# Sheet1.net
KiCad netlist of a schematic drawn in Altium Designer
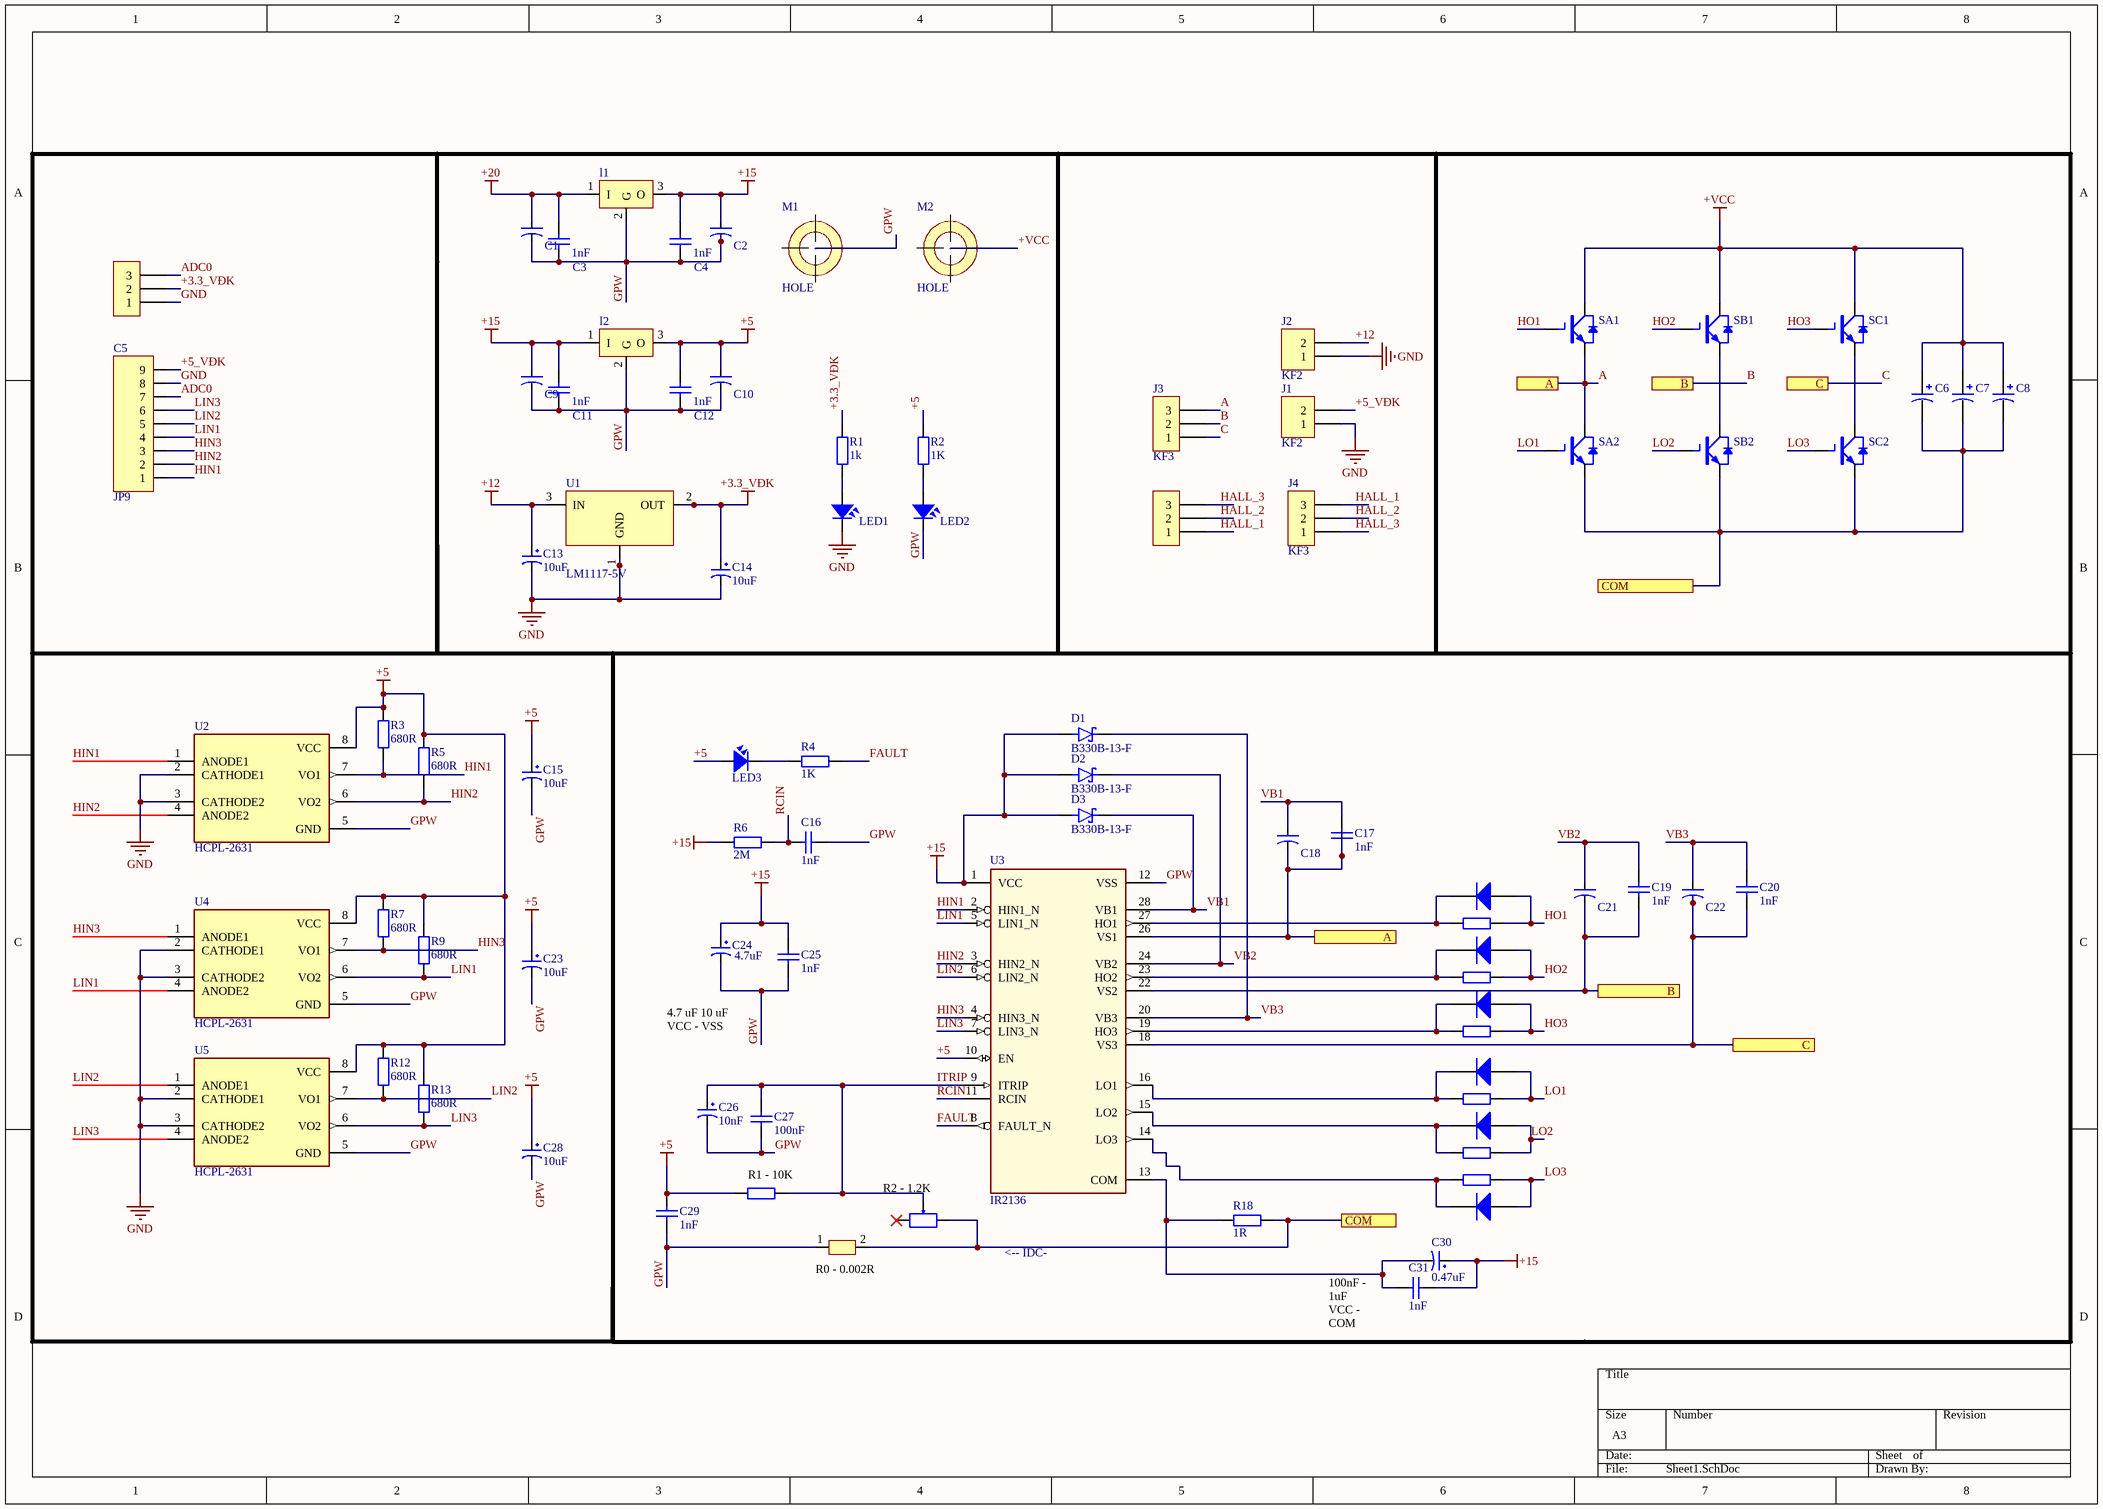
[diagram p0: Sheet1.SchDoc]

(export (version "E")
  (design (tool "Eeschema 10.0.6"))
  (components
    (comp (ref "*1")
      (value "Component_1")
      (footprint "PCBComponent_1")
      (libsource (lib "Shunt") (part "Component_1"))
    )
    (comp (ref "C1")
      (value "CN-ALU-DIP")
      (footprint "CA-ALU-5")
      (description "Capacitor (Semiconductor SIM Model)")
      (fields (field (name "PUBLISHER") "Altium Limited"))
      (libsource (lib "TechMT.VN_Lib_Project v2") (part "CN-ALU-DIP"))
    )
    (comp (ref "C2")
      (value "CN-ALU-DIP")
      (footprint "CA-ALU-5")
      (description "Capacitor (Semiconductor SIM Model)")
      (fields (field (name "PUBLISHER") "Altium Limited"))
      (libsource (lib "TechMT.VN_Lib_Project v2") (part "CN-ALU-DIP"))
    )
    (comp (ref "C3")
      (value "1nF")
      (footprint "tu 1206")
      (description "Dán")
      (libsource (lib "Altium_Lib_by_KhueNguyenCreator") (part "Tu 1206 470pF 50V 10%"))
    )
    (comp (ref "C4")
      (value "1nF")
      (footprint "tu 1206")
      (description "Dán")
      (libsource (lib "Altium_Lib_by_KhueNguyenCreator") (part "Tu 1206 470pF 50V 10%"))
    )
    (comp (ref "C5")
      (value "JP9")
      (footprint "JP9-C1T")
      (description "WR-PHD 2.54 mm Angled Socket Header")
      (fields
        (field (name "MANUFACTURER") "Würth Elektronik eiSos GmbH")
        (field (name "PARTNO") "613009143121")
        (field (name "CREATED BY") "Karrer Zheng")
      )
      (libsource (lib "TechMT.VN_Lib_Project v2") (part "JP9"))
    )
    (comp (ref "C6")
      (value "150uF - 450V")
      (footprint "CAP_ALUM_D160_S75_H250")
      (description "CAP ALUM 1000uF 20% 63V RADIAL")
      (fields (field (name "MPN") "CLA4514"))
      (libsource (lib "BYTECH_HW_LIB_2019 (1)") (part "CLA4514"))
    )
    (comp (ref "C7")
      (value "150uF - 450V")
      (footprint "CAP_ALUM_D160_S75_H250")
      (description "CAP ALUM 1000uF 20% 63V RADIAL")
      (fields (field (name "MPN") "CLA4514"))
      (libsource (lib "BYTECH_HW_LIB_2019 (1)") (part "CLA4514"))
    )
    (comp (ref "C8")
      (value "150uF - 450V")
      (footprint "CAP_ALUM_D160_S75_H250")
      (description "CAP ALUM 1000uF 20% 63V RADIAL")
      (fields (field (name "MPN") "CLA4514"))
      (libsource (lib "BYTECH_HW_LIB_2019 (1)") (part "CLA4514"))
    )
    (comp (ref "C9")
      (value "CN-ALU-DIP")
      (footprint "CA-ALU-5")
      (description "Capacitor (Semiconductor SIM Model)")
      (fields (field (name "PUBLISHER") "Altium Limited"))
      (libsource (lib "TechMT.VN_Lib_Project v2") (part "CN-ALU-DIP"))
    )
    (comp (ref "C10")
      (value "CN-ALU-DIP")
      (footprint "CA-ALU-5")
      (description "Capacitor (Semiconductor SIM Model)")
      (fields (field (name "PUBLISHER") "Altium Limited"))
      (libsource (lib "TechMT.VN_Lib_Project v2") (part "CN-ALU-DIP"))
    )
    (comp (ref "C11")
      (value "1nF")
      (footprint "tu 1206")
      (description "Dán")
      (libsource (lib "Altium_Lib_by_KhueNguyenCreator") (part "Tu 1206 470pF 50V 10%"))
    )
    (comp (ref "C12")
      (value "1nF")
      (footprint "tu 1206")
      (description "Dán")
      (libsource (lib "Altium_Lib_by_KhueNguyenCreator") (part "Tu 1206 470pF 50V 10%"))
    )
    (comp (ref "C13")
      (value "10uF")
      (footprint "tu tantalum smd3216")
      (description "Dán")
      (libsource (lib "Altium_Lib_by_KhueNguyenCreator") (part "Tu tantalum 10uF 16V SMD3216"))
    )
    (comp (ref "C14")
      (value "10uF")
      (footprint "tu tantalum smd3216")
      (description "Dán")
      (libsource (lib "Altium_Lib_by_KhueNguyenCreator") (part "Tu tantalum 10uF 16V SMD3216"))
    )
    (comp (ref "C15")
      (value "10uF")
      (footprint "tu tantalum smd3216")
      (description "Dán")
      (libsource (lib "Altium_Lib_by_KhueNguyenCreator") (part "Tu tantalum 10uF 16V SMD3216"))
    )
    (comp (ref "C16")
      (value "1nF")
      (footprint "tu 1206")
      (description "Dán")
      (libsource (lib "Altium_Lib_by_KhueNguyenCreator") (part "Tu 1206 470pF 50V 10%"))
    )
    (comp (ref "C17")
      (value "1nF")
      (footprint "tu 1206")
      (description "Dán")
      (libsource (lib "Altium_Lib_by_KhueNguyenCreator") (part "Tu 1206 470pF 50V 10%"))
    )
    (comp (ref "C18")
      (value "CN-ALU-DIP")
      (footprint "CA-ALU-5")
      (description "Capacitor (Semiconductor SIM Model)")
      (fields (field (name "PUBLISHER") "Altium Limited"))
      (libsource (lib "TechMT.VN_Lib_Project v2") (part "CN-ALU-DIP"))
    )
    (comp (ref "C19")
      (value "1nF")
      (footprint "tu 1206")
      (description "Dán")
      (libsource (lib "Altium_Lib_by_KhueNguyenCreator") (part "Tu 1206 470pF 50V 10%"))
    )
    (comp (ref "C20")
      (value "1nF")
      (footprint "tu 1206")
      (description "Dán")
      (libsource (lib "Altium_Lib_by_KhueNguyenCreator") (part "Tu 1206 470pF 50V 10%"))
    )
    (comp (ref "C21")
      (value "CN-ALU-DIP")
      (footprint "CA-ALU-5")
      (description "Capacitor (Semiconductor SIM Model)")
      (fields (field (name "PUBLISHER") "Altium Limited"))
      (libsource (lib "TechMT.VN_Lib_Project v2") (part "CN-ALU-DIP"))
    )
    (comp (ref "C22")
      (value "CN-ALU-DIP")
      (footprint "CA-ALU-5")
      (description "Capacitor (Semiconductor SIM Model)")
      (fields (field (name "PUBLISHER") "Altium Limited"))
      (libsource (lib "TechMT.VN_Lib_Project v2") (part "CN-ALU-DIP"))
    )
    (comp (ref "C23")
      (value "10uF")
      (footprint "tu tantalum smd3216")
      (description "Dán")
      (libsource (lib "Altium_Lib_by_KhueNguyenCreator") (part "Tu tantalum 10uF 16V SMD3216"))
    )
    (comp (ref "C24")
      (value "4.7uF")
      (footprint "tu tantalum smd3216")
      (description "Dán")
      (libsource (lib "Altium_Lib_by_KhueNguyenCreator") (part "Tu tantalum 10uF 16V SMD3216"))
    )
    (comp (ref "C25")
      (value "1nF")
      (footprint "tu 1206")
      (description "Dán")
      (libsource (lib "Altium_Lib_by_KhueNguyenCreator") (part "Tu 1206 470pF 50V 10%"))
    )
    (comp (ref "C26")
      (value "10nF")
      (footprint "tu tantalum smd3216")
      (description "Dán")
      (libsource (lib "Altium_Lib_by_KhueNguyenCreator") (part "Tu tantalum 10uF 16V SMD3216"))
    )
    (comp (ref "C27")
      (value "100nF")
      (footprint "tu 1206")
      (description "Dán")
      (libsource (lib "Altium_Lib_by_KhueNguyenCreator") (part "Tu 1206 470pF 50V 10%"))
    )
    (comp (ref "C28")
      (value "10uF")
      (footprint "tu tantalum smd3216")
      (description "Dán")
      (libsource (lib "Altium_Lib_by_KhueNguyenCreator") (part "Tu tantalum 10uF 16V SMD3216"))
    )
    (comp (ref "C29")
      (value "1nF")
      (footprint "tu 1206")
      (description "Dán")
      (libsource (lib "Altium_Lib_by_KhueNguyenCreator") (part "Tu 1206 470pF 50V 10%"))
    )
    (comp (ref "C30")
      (value "0.47uF")
      (footprint "tu tantalum smd3216")
      (description "Dán")
      (libsource (lib "") (part "Tu tantalum 10uF 16V SMD3216_1"))
    )
    (comp (ref "C31")
      (value "1nF")
      (footprint "tu 1206")
      (description "Dán")
      (libsource (lib "Altium_Lib_by_KhueNguyenCreator") (part "Tu 1206 470pF 50V 10%"))
    )
    (comp (ref "D1")
      (value "B330B-13-F")
      (footprint "DIOM5336X240N")
      (description "Diode Schottky 30 V 3A Surface Mount SMB")
      (fields (field (name "MF") "Diodes Inc."))
      (libsource (lib "Do214AA_SMB_Diode") (part "B330B-13-F"))
    )
    (comp (ref "D2")
      (value "B330B-13-F")
      (footprint "DIOM5336X240N")
      (description "Diode Schottky 30 V 3A Surface Mount SMB")
      (fields (field (name "MF") "Diodes Inc."))
      (libsource (lib "Do214AA_SMB_Diode") (part "B330B-13-F"))
    )
    (comp (ref "D3")
      (value "B330B-13-F")
      (footprint "DIOM5336X240N")
      (description "Diode Schottky 30 V 3A Surface Mount SMB")
      (fields (field (name "MF") "Diodes Inc."))
      (libsource (lib "Do214AA_SMB_Diode") (part "B330B-13-F"))
    )
    (comp (ref "D4")
      (value "SS14")
      (footprint "DIODE SMA")
      (description "Dán")
      (libsource (lib "Altium_Lib_by_KhueNguyenCreator") (part "Diode SS14 ( 1N5819)"))
    )
    (comp (ref "D5")
      (value "SS14")
      (footprint "DIODE SMA")
      (description "Dán")
      (libsource (lib "Altium_Lib_by_KhueNguyenCreator") (part "Diode SS14 ( 1N5819)"))
    )
    (comp (ref "D6")
      (value "SS14")
      (footprint "DIODE SMA")
      (description "Dán")
      (libsource (lib "Altium_Lib_by_KhueNguyenCreator") (part "Diode SS14 ( 1N5819)"))
    )
    (comp (ref "D7")
      (value "SS14")
      (footprint "DIODE SMA")
      (description "Dán")
      (libsource (lib "Altium_Lib_by_KhueNguyenCreator") (part "Diode SS14 ( 1N5819)"))
    )
    (comp (ref "D8")
      (value "SS14")
      (footprint "DIODE SMA")
      (description "Dán")
      (libsource (lib "Altium_Lib_by_KhueNguyenCreator") (part "Diode SS14 ( 1N5819)"))
    )
    (comp (ref "D9")
      (value "SS14")
      (footprint "DIODE SMA")
      (description "Dán")
      (libsource (lib "Altium_Lib_by_KhueNguyenCreator") (part "Diode SS14 ( 1N5819)"))
    )
    (comp (ref "H1")
      (value "Header 3P 2.54 Duc Thang")
      (footprint "XH2.54M-3")
      (description "Cắm")
      (libsource (lib "Altium_Lib_by_KhueNguyenCreator") (part "Header 3P 2.54 Duc Thang"))
    )
    (comp (ref "H2")
      (value "Header 3P 2.54 Duc Thang")
      (footprint "XH2.54M-3")
      (description "Cắm")
      (libsource (lib "Altium_Lib_by_KhueNguyenCreator") (part "Header 3P 2.54 Duc Thang"))
    )
    (comp (ref "J1")
      (value "KF2")
      (footprint "KF2-3.5")
      (fields
        (field (name "MANUFACTURER") "Würth Elektronik eiSos GmbH")
        (field (name "PARTNO") "691103110002")
        (field (name "CREATED BY") "Karrer Zheng")
      )
      (libsource (lib "TechMT.VN_Lib_Project v2") (part "KF2"))
    )
    (comp (ref "J2")
      (value "KF2")
      (footprint "KF2-3.5")
      (fields
        (field (name "MANUFACTURER") "Würth Elektronik eiSos GmbH")
        (field (name "PARTNO") "691103110002")
        (field (name "CREATED BY") "Karrer Zheng")
      )
      (libsource (lib "TechMT.VN_Lib_Project v2") (part "KF2"))
    )
    (comp (ref "J3")
      (value "KF3")
      (footprint "KF3-8.5")
      (fields
        (field (name "MANUFACTURER") "Würth Elektronik eiSos GmbH")
        (field (name "PARTNO") "691103110003")
        (field (name "CREATED BY") "Karrer Zheng")
      )
      (libsource (lib "TechMT.VN_Lib_Project v2") (part "KF3"))
    )
    (comp (ref "J4")
      (value "KF3")
      (footprint "KF3-3.5")
      (fields
        (field (name "MANUFACTURER") "Würth Elektronik eiSos GmbH")
        (field (name "PARTNO") "691103110003")
        (field (name "CREATED BY") "Karrer Zheng")
      )
      (libsource (lib "TechMT.VN_Lib_Project v2") (part "KF3"))
    )
    (comp (ref "l1")
      (value "LM78xx")
      (footprint "TO220-123")
      (description "Positive Voltage Regulator")
      (fields (field (name "PUBLISHER") "Altium Limited"))
      (libsource (lib "TechMT.VN_Lib_Project v2") (part "LM78xx"))
    )
    (comp (ref "l2")
      (value "LM78xx")
      (footprint "TO220-123")
      (description "Positive Voltage Regulator")
      (fields (field (name "PUBLISHER") "Altium Limited"))
      (libsource (lib "TechMT.VN_Lib_Project v2") (part "LM78xx"))
    )
    (comp (ref "LED1")
      (value "LED")
      (footprint "LED-1206-Blue")
      (libsource (lib "TechMT.VN_Lib_Project v2") (part "LED SMD"))
    )
    (comp (ref "LED2")
      (value "LED")
      (footprint "LED-1206-Blue")
      (libsource (lib "TechMT.VN_Lib_Project v2") (part "LED SMD"))
    )
    (comp (ref "LED3")
      (value "LED")
      (footprint "LED-1206-Blue")
      (libsource (lib "TechMT.VN_Lib_Project v2") (part "LED SMD"))
    )
    (comp (ref "M1")
      (value "HOLE")
      (footprint "HOLE_3MM_5MM")
      (description "HOLE 2_4/2_5/3_5/3_6")
      (fields (field (name "MPN") "None"))
      (libsource (lib "BYTECH_HW_LIB_2019 (1)") (part "HOLE_2_4/2_5/3_5/3_6"))
    )
    (comp (ref "M2")
      (value "HOLE")
      (footprint "HOLE_3MM_5MM")
      (description "HOLE 2_4/2_5/3_5/3_6")
      (fields (field (name "MPN") "None"))
      (libsource (lib "BYTECH_HW_LIB_2019 (1)") (part "HOLE_2_4/2_5/3_5/3_6"))
    )
    (comp (ref "R1")
      (value "1k")
      (footprint "tro smd 1206")
      (description "Dán")
      (libsource (lib "Altium_Lib_by_KhueNguyenCreator") (part "Tro 1206 5% 680R"))
    )
    (comp (ref "R2")
      (value "1K")
      (footprint "tro smd 1206")
      (description "Dán")
      (libsource (lib "Altium_Lib_by_KhueNguyenCreator") (part "Tro 1206 5% 680R"))
    )
    (comp (ref "R3")
      (value "680R")
      (footprint "tro smd 1206")
      (description "Dán")
      (libsource (lib "Altium_Lib_by_KhueNguyenCreator") (part "Tro 1206 5% 680R"))
    )
    (comp (ref "R4")
      (value "1K")
      (footprint "tro smd 1206")
      (description "Dán")
      (libsource (lib "Altium_Lib_by_KhueNguyenCreator") (part "Tro 1206 5% 680R"))
    )
    (comp (ref "R5")
      (value "680R")
      (footprint "tro smd 1206")
      (description "Dán")
      (libsource (lib "Altium_Lib_by_KhueNguyenCreator") (part "Tro 1206 5% 680R"))
    )
    (comp (ref "R6")
      (value "2M")
      (footprint "tro smd 1206")
      (description "Dán")
      (libsource (lib "Altium_Lib_by_KhueNguyenCreator") (part "Tro 1206 5% 680R"))
    )
    (comp (ref "R7")
      (value "680R")
      (footprint "tro smd 1206")
      (description "Dán")
      (libsource (lib "Altium_Lib_by_KhueNguyenCreator") (part "Tro 1206 5% 680R"))
    )
    (comp (ref "R8")
      (value "680R")
      (footprint "tro smd 1206")
      (description "Dán")
      (libsource (lib "Altium_Lib_by_KhueNguyenCreator") (part "Tro 1206 5% 680R"))
    )
    (comp (ref "R9")
      (value "680R")
      (footprint "tro smd 1206")
      (description "Dán")
      (libsource (lib "Altium_Lib_by_KhueNguyenCreator") (part "Tro 1206 5% 680R"))
    )
    (comp (ref "R10")
      (value "680R")
      (footprint "tro smd 1206")
      (description "Dán")
      (libsource (lib "Altium_Lib_by_KhueNguyenCreator") (part "Tro 1206 5% 680R"))
    )
    (comp (ref "R11")
      (value "680R")
      (footprint "tro smd 1206")
      (description "Dán")
      (libsource (lib "Altium_Lib_by_KhueNguyenCreator") (part "Tro 1206 5% 680R"))
    )
    (comp (ref "R12")
      (value "680R")
      (footprint "tro smd 1206")
      (description "Dán")
      (libsource (lib "Altium_Lib_by_KhueNguyenCreator") (part "Tro 1206 5% 680R"))
    )
    (comp (ref "R13")
      (value "680R")
      (footprint "tro smd 1206")
      (description "Dán")
      (libsource (lib "Altium_Lib_by_KhueNguyenCreator") (part "Tro 1206 5% 680R"))
    )
    (comp (ref "R14")
      (value "680R")
      (footprint "tro smd 1206")
      (description "Dán")
      (libsource (lib "Altium_Lib_by_KhueNguyenCreator") (part "Tro 1206 5% 680R"))
    )
    (comp (ref "R15")
      (value "680R")
      (footprint "tro smd 1206")
      (description "Dán")
      (libsource (lib "Altium_Lib_by_KhueNguyenCreator") (part "Tro 1206 5% 680R"))
    )
    (comp (ref "R16")
      (value "680R")
      (footprint "tro smd 1206")
      (description "Dán")
      (libsource (lib "Altium_Lib_by_KhueNguyenCreator") (part "Tro 1206 5% 680R"))
    )
    (comp (ref "R17")
      (value "5.1K")
      (footprint "tro smd 1206")
      (description "Dán")
      (libsource (lib "Altium_Lib_by_KhueNguyenCreator") (part "Tro 1206 5% 680R"))
    )
    (comp (ref "R18")
      (value "1R")
      (footprint "tro smd 1206")
      (description "Dán")
      (libsource (lib "Altium_Lib_by_KhueNguyenCreator") (part "Tro 1206 5% 680R"))
    )
    (comp (ref "R19")
      (value "6K")
      (footprint "Bien Tro Vi Chinh Dung")
      (description "Cắm")
      (libsource (lib "Altium_Lib_by_KhueNguyenCreator") (part "Bien Tro Tinh Chinh 100R Dung"))
    )
    (comp (ref "SA1")
      (value "FGA25N120ANTD")
      (footprint "TO545P500X1560X1990-3P")
      (description "IGBT NPT and Trench 1200V 50A 312W Through Hole TO-3P")
      (fields
        (field (name "DIGI-KEY_PART_NUMBER") "FGA25N120ANTDTU-ND")
        (field (name "MF") "ON Semiconductor")
      )
      (libsource (lib "IGBT 5.45") (part "FGA25N120ANTD"))
    )
    (comp (ref "SA2")
      (value "FGA25N120ANTD")
      (footprint "TO545P500X1560X1990-3P")
      (description "IGBT NPT and Trench 1200V 50A 312W Through Hole TO-3P")
      (fields
        (field (name "DIGI-KEY_PART_NUMBER") "FGA25N120ANTDTU-ND")
        (field (name "MF") "ON Semiconductor")
      )
      (libsource (lib "IGBT 5.45") (part "FGA25N120ANTD"))
    )
    (comp (ref "SB1")
      (value "FGA25N120ANTD")
      (footprint "TO545P500X1560X1990-3P")
      (description "IGBT NPT and Trench 1200V 50A 312W Through Hole TO-3P")
      (fields
        (field (name "DIGI-KEY_PART_NUMBER") "FGA25N120ANTDTU-ND")
        (field (name "MF") "ON Semiconductor")
      )
      (libsource (lib "IGBT 5.45") (part "FGA25N120ANTD"))
    )
    (comp (ref "SB2")
      (value "FGA25N120ANTD")
      (footprint "TO545P500X1560X1990-3P")
      (description "IGBT NPT and Trench 1200V 50A 312W Through Hole TO-3P")
      (fields
        (field (name "DIGI-KEY_PART_NUMBER") "FGA25N120ANTDTU-ND")
        (field (name "MF") "ON Semiconductor")
      )
      (libsource (lib "IGBT 5.45") (part "FGA25N120ANTD"))
    )
    (comp (ref "SC1")
      (value "FGA25N120ANTD")
      (footprint "TO545P500X1560X1990-3P")
      (description "IGBT NPT and Trench 1200V 50A 312W Through Hole TO-3P")
      (fields
        (field (name "DIGI-KEY_PART_NUMBER") "FGA25N120ANTDTU-ND")
        (field (name "MF") "ON Semiconductor")
      )
      (libsource (lib "IGBT 5.45") (part "FGA25N120ANTD"))
    )
    (comp (ref "SC2")
      (value "FGA25N120ANTD")
      (footprint "TO545P500X1560X1990-3P")
      (description "IGBT NPT and Trench 1200V 50A 312W Through Hole TO-3P")
      (fields
        (field (name "DIGI-KEY_PART_NUMBER") "FGA25N120ANTDTU-ND")
        (field (name "MF") "ON Semiconductor")
      )
      (libsource (lib "IGBT 5.45") (part "FGA25N120ANTD"))
    )
    (comp (ref "U1")
      (value "LM1117-5V")
      (footprint "SOT223")
      (description "800mA Low-Dropout Linear Regulator")
      (fields (field (name "CREATOR") "Nguyen Ba Bien"))
      (libsource (lib "TechMT.VN_Lib_Project v2") (part "LM1117"))
    )
    (comp (ref "U2")
      (value "HCPL-2631")
      (footprint "DIP762W65P254L965H470Q8")
      (fields (field (name "MF") "Broadcom Limited"))
      (libsource (lib "HCPL-2631") (part "HCPL-2631"))
    )
    (comp (ref "U3")
      (value "IR2136")
      (footprint "DIP1524W46P254L3740H635Q28B")
      (description "High Voltage Gate Driver IC")
      (fields (field (name "MANUFACTURER") "Infineon Technologies"))
      (libsource (lib "ir2132dip") (part "IR2136"))
    )
    (comp (ref "U4")
      (value "HCPL-2631")
      (footprint "DIP762W65P254L965H470Q8")
      (fields (field (name "MF") "Broadcom Limited"))
      (libsource (lib "HCPL-2631") (part "HCPL-2631"))
    )
    (comp (ref "U5")
      (value "HCPL-2631")
      (footprint "DIP762W65P254L965H470Q8")
      (fields (field (name "MF") "Broadcom Limited"))
      (libsource (lib "HCPL-2631") (part "HCPL-2631"))
    )
  )
  (nets
    (net (code "1") (name "+3.3_VĐK") (class "Default")
      (node (ref "C14") (pin "1") (pinfunction "1_1") (pintype "passive"))
      (node (ref "H1") (pin "2") (pinfunction "2_2") (pintype "passive"))
      (node (ref "R1") (pin "2") (pinfunction "2_2") (pintype "passive"))
      (node (ref "U1") (pin "2") (pinfunction "OUT_2") (pintype "passive"))
    )
    (net (code "2") (name "+5") (class "Default")
      (node (ref "C10") (pin "1") (pinfunction "1_1") (pintype "passive"))
      (node (ref "C12") (pin "1") (pinfunction "1_1") (pintype "passive"))
      (node (ref "C15") (pin "1") (pinfunction "1_1") (pintype "passive"))
      (node (ref "C23") (pin "1") (pinfunction "1_1") (pintype "passive"))
      (node (ref "C28") (pin "1") (pinfunction "1_1") (pintype "passive"))
      (node (ref "C29") (pin "1") (pinfunction "1_1") (pintype "passive"))
      (node (ref "LED3") (pin "1") (pinfunction "1_1") (pintype "passive"))
      (node (ref "R12") (pin "2") (pinfunction "2_2") (pintype "passive"))
      (node (ref "R13") (pin "2") (pinfunction "2_2") (pintype "passive"))
      (node (ref "R17") (pin "2") (pinfunction "2_2") (pintype "passive"))
      (node (ref "R2") (pin "2") (pinfunction "2_2") (pintype "passive"))
      (node (ref "R3") (pin "2") (pinfunction "2_2") (pintype "passive"))
      (node (ref "R5") (pin "2") (pinfunction "2_2") (pintype "passive"))
      (node (ref "R7") (pin "2") (pinfunction "2_2") (pintype "passive"))
      (node (ref "R9") (pin "2") (pinfunction "2_2") (pintype "passive"))
      (node (ref "U2") (pin "8") (pinfunction "VCC_8") (pintype "power_in"))
      (node (ref "U3") (pin "10") (pinfunction "EN_10") (pintype "bidirectional"))
      (node (ref "U4") (pin "8") (pinfunction "VCC_8") (pintype "power_in"))
      (node (ref "U5") (pin "8") (pinfunction "VCC_8") (pintype "power_in"))
      (node (ref "l2") (pin "3") (pinfunction "O_3") (pintype "power_in"))
    )
    (net (code "3") (name "+12") (class "Default")
      (node (ref "C13") (pin "1") (pinfunction "1_1") (pintype "passive"))
      (node (ref "J2") (pin "2") (pinfunction "2_2") (pintype "passive"))
      (node (ref "U1") (pin "3") (pinfunction "IN_3") (pintype "passive"))
    )
    (net (code "4") (name "+15") (class "Default")
      (node (ref "C11") (pin "1") (pinfunction "1_1") (pintype "passive"))
      (node (ref "C2") (pin "1") (pinfunction "1_1") (pintype "passive"))
      (node (ref "C24") (pin "1") (pinfunction "1_1") (pintype "passive"))
      (node (ref "C25") (pin "1") (pinfunction "1_1") (pintype "passive"))
      (node (ref "C30") (pin "1") (pinfunction "1_1") (pintype "passive"))
      (node (ref "C31") (pin "1") (pinfunction "1_1") (pintype "passive"))
      (node (ref "C4") (pin "1") (pinfunction "1_1") (pintype "passive"))
      (node (ref "C9") (pin "1") (pinfunction "1_1") (pintype "passive"))
      (node (ref "D1") (pin "A") (pinfunction "A_A") (pintype "passive"))
      (node (ref "D2") (pin "A") (pinfunction "A_A") (pintype "passive"))
      (node (ref "D3") (pin "A") (pinfunction "A_A") (pintype "passive"))
      (node (ref "R6") (pin "2") (pinfunction "2_2") (pintype "passive"))
      (node (ref "U3") (pin "1") (pinfunction "VCC_1") (pintype "power_in"))
      (node (ref "l1") (pin "3") (pinfunction "O_3") (pintype "power_in"))
      (node (ref "l2") (pin "1") (pinfunction "I_1") (pintype "power_in"))
    )
    (net (code "5") (name "+20") (class "Default")
      (node (ref "C1") (pin "1") (pinfunction "1_1") (pintype "passive"))
      (node (ref "C3") (pin "1") (pinfunction "1_1") (pintype "passive"))
      (node (ref "l1") (pin "1") (pinfunction "I_1") (pintype "power_in"))
    )
    (net (code "6") (name "+VCC") (class "Default")
      (node (ref "C6") (pin "1") (pinfunction "1_1") (pintype "passive"))
      (node (ref "C7") (pin "1") (pinfunction "1_1") (pintype "passive"))
      (node (ref "C8") (pin "1") (pinfunction "1_1") (pintype "passive"))
      (node (ref "SA1") (pin "2") (pinfunction "C_2") (pintype "passive"))
      (node (ref "SB1") (pin "2") (pinfunction "C_2") (pintype "passive"))
      (node (ref "SC1") (pin "2") (pinfunction "C_2") (pintype "passive"))
    )
    (net (code "7") (name "/+5_VĐK") (class "Default")
      (node (ref "C5") (pin "9") (pinfunction "9_9") (pintype "passive"))
      (node (ref "J1") (pin "2") (pinfunction "2_2") (pintype "passive"))
    )
    (net (code "8") (name "/A") (class "Default")
      (node (ref "C17") (pin "2") (pinfunction "2_2") (pintype "passive"))
      (node (ref "C18") (pin "2") (pinfunction "2_2") (pintype "passive"))
      (node (ref "J3") (pin "3") (pinfunction "3_3") (pintype "passive"))
      (node (ref "SA1") (pin "3") (pinfunction "E_3") (pintype "passive"))
      (node (ref "SA2") (pin "2") (pinfunction "C_2") (pintype "passive"))
      (node (ref "U3") (pin "26") (pinfunction "VS1_26") (pintype "power_in"))
    )
    (net (code "9") (name "/ADC0") (class "Default")
      (node (ref "C5") (pin "7") (pinfunction "7_7") (pintype "passive"))
      (node (ref "H1") (pin "3") (pinfunction "3_3") (pintype "passive"))
    )
    (net (code "10") (name "/B") (class "Default")
      (node (ref "C19") (pin "2") (pinfunction "2_2") (pintype "passive"))
      (node (ref "C21") (pin "2") (pinfunction "2_2") (pintype "passive"))
      (node (ref "J3") (pin "2") (pinfunction "2_2") (pintype "passive"))
      (node (ref "U3") (pin "22") (pinfunction "VS2_22") (pintype "power_in"))
    )
    (net (code "11") (name "/C") (class "Default")
      (node (ref "C20") (pin "2") (pinfunction "2_2") (pintype "passive"))
      (node (ref "C22") (pin "2") (pinfunction "2_2") (pintype "passive"))
      (node (ref "J3") (pin "1") (pinfunction "1_1") (pintype "passive"))
      (node (ref "U3") (pin "18") (pinfunction "VS3_18") (pintype "power_in"))
    )
    (net (code "12") (name "/COM") (class "Default")
      (node (ref "*1") (pin "2") (pinfunction "18_2") (pintype "passive"))
      (node (ref "C6") (pin "2") (pinfunction "2_2") (pintype "passive"))
      (node (ref "C7") (pin "2") (pinfunction "2_2") (pintype "passive"))
      (node (ref "C8") (pin "2") (pinfunction "2_2") (pintype "passive"))
      (node (ref "R18") (pin "1") (pinfunction "1_1") (pintype "passive"))
      (node (ref "R19") (pin "3") (pinfunction "3_3") (pintype "passive"))
      (node (ref "SA2") (pin "3") (pinfunction "E_3") (pintype "passive"))
      (node (ref "SB2") (pin "3") (pinfunction "E_3") (pintype "passive"))
      (node (ref "SC2") (pin "3") (pinfunction "E_3") (pintype "passive"))
    )
    (net (code "13") (name "/FAULT") (class "Default")
      (node (ref "R4") (pin "2") (pinfunction "2_2") (pintype "passive"))
      (node (ref "U3") (pin "8") (pinfunction "FAULT_N_8") (pintype "output"))
    )
    (net (code "14") (name "/GPW") (class "Default")
      (node (ref "*1") (pin "1") (pinfunction "17_1") (pintype "passive"))
      (node (ref "C1") (pin "2") (pinfunction "2_2") (pintype "passive"))
      (node (ref "C10") (pin "2") (pinfunction "2_2") (pintype "passive"))
      (node (ref "C11") (pin "2") (pinfunction "2_2") (pintype "passive"))
      (node (ref "C12") (pin "2") (pinfunction "2_2") (pintype "passive"))
      (node (ref "C15") (pin "2") (pinfunction "2_2") (pintype "passive"))
      (node (ref "C16") (pin "2") (pinfunction "2_2") (pintype "passive"))
      (node (ref "C2") (pin "2") (pinfunction "2_2") (pintype "passive"))
      (node (ref "C23") (pin "2") (pinfunction "2_2") (pintype "passive"))
      (node (ref "C24") (pin "2") (pinfunction "2_2") (pintype "passive"))
      (node (ref "C25") (pin "2") (pinfunction "2_2") (pintype "passive"))
      (node (ref "C26") (pin "2") (pinfunction "2_2") (pintype "passive"))
      (node (ref "C27") (pin "2") (pinfunction "2_2") (pintype "passive"))
      (node (ref "C28") (pin "2") (pinfunction "2_2") (pintype "passive"))
      (node (ref "C29") (pin "2") (pinfunction "2_2") (pintype "passive"))
      (node (ref "C3") (pin "2") (pinfunction "2_2") (pintype "passive"))
      (node (ref "C4") (pin "2") (pinfunction "2_2") (pintype "passive"))
      (node (ref "C9") (pin "2") (pinfunction "2_2") (pintype "passive"))
      (node (ref "LED2") (pin "2") (pinfunction "2_2") (pintype "passive"))
      (node (ref "U2") (pin "5") (pinfunction "GND_5") (pintype "power_in"))
      (node (ref "U3") (pin "12") (pinfunction "VSS_12") (pintype "power_in"))
      (node (ref "U4") (pin "5") (pinfunction "GND_5") (pintype "power_in"))
      (node (ref "U5") (pin "5") (pinfunction "GND_5") (pintype "power_in"))
      (node (ref "l1") (pin "2") (pinfunction "G_2") (pintype "power_in"))
      (node (ref "l2") (pin "2") (pinfunction "G_2") (pintype "power_in"))
    )
    (net (code "15") (name "/HALL_1") (class "Default")
      (node (ref "H2") (pin "1") (pinfunction "1_1") (pintype "passive"))
      (node (ref "J4") (pin "3") (pinfunction "3_3") (pintype "passive"))
    )
    (net (code "16") (name "/HALL_2") (class "Default")
      (node (ref "H2") (pin "2") (pinfunction "2_2") (pintype "passive"))
      (node (ref "J4") (pin "2") (pinfunction "2_2") (pintype "passive"))
    )
    (net (code "17") (name "/HALL_3") (class "Default")
      (node (ref "H2") (pin "3") (pinfunction "3_3") (pintype "passive"))
      (node (ref "J4") (pin "1") (pinfunction "1_1") (pintype "passive"))
    )
    (net (code "18") (name "/HIN1") (class "Default")
      (node (ref "C5") (pin "1") (pinfunction "1_1") (pintype "passive"))
      (node (ref "R3") (pin "1") (pinfunction "1_1") (pintype "passive"))
      (node (ref "U2") (pin "1") (pinfunction "ANODE1_1") (pintype "passive"))
      (node (ref "U2") (pin "7") (pinfunction "VO1_7") (pintype "output"))
      (node (ref "U3") (pin "2") (pinfunction "HIN1_N_2") (pintype "input"))
    )
    (net (code "19") (name "/HIN2") (class "Default")
      (node (ref "C5") (pin "2") (pinfunction "2_2") (pintype "passive"))
      (node (ref "R5") (pin "1") (pinfunction "1_1") (pintype "passive"))
      (node (ref "U2") (pin "4") (pinfunction "ANODE2_4") (pintype "passive"))
      (node (ref "U2") (pin "6") (pinfunction "VO2_6") (pintype "output"))
      (node (ref "U3") (pin "3") (pinfunction "HIN2_N_3") (pintype "input"))
    )
    (net (code "20") (name "/HIN3") (class "Default")
      (node (ref "C5") (pin "3") (pinfunction "3_3") (pintype "passive"))
      (node (ref "R7") (pin "1") (pinfunction "1_1") (pintype "passive"))
      (node (ref "U3") (pin "4") (pinfunction "HIN3_N_4") (pintype "input"))
      (node (ref "U4") (pin "1") (pinfunction "ANODE1_1") (pintype "passive"))
      (node (ref "U4") (pin "7") (pinfunction "VO1_7") (pintype "output"))
    )
    (net (code "21") (name "/HO1") (class "Default")
      (node (ref "D4") (pin "1") (pinfunction "A_1") (pintype "passive"))
      (node (ref "R8") (pin "1") (pinfunction "1_1") (pintype "passive"))
      (node (ref "SA1") (pin "1") (pinfunction "G_1") (pintype "passive"))
    )
    (net (code "22") (name "/HO2") (class "Default")
      (node (ref "D5") (pin "1") (pinfunction "A_1") (pintype "passive"))
      (node (ref "R10") (pin "1") (pinfunction "1_1") (pintype "passive"))
      (node (ref "SB1") (pin "1") (pinfunction "G_1") (pintype "passive"))
    )
    (net (code "23") (name "/HO3") (class "Default")
      (node (ref "D6") (pin "1") (pinfunction "A_1") (pintype "passive"))
      (node (ref "R11") (pin "1") (pinfunction "1_1") (pintype "passive"))
      (node (ref "SC1") (pin "1") (pinfunction "G_1") (pintype "passive"))
    )
    (net (code "24") (name "/ITRIP") (class "Default")
      (node (ref "C26") (pin "1") (pinfunction "1_1") (pintype "passive"))
      (node (ref "C27") (pin "1") (pinfunction "1_1") (pintype "passive"))
      (node (ref "R17") (pin "1") (pinfunction "1_1") (pintype "passive"))
      (node (ref "R19") (pin "2") (pinfunction "2_2") (pintype "passive"))
      (node (ref "U3") (pin "9") (pinfunction "ITRIP_9") (pintype "input"))
    )
    (net (code "25") (name "/LIN1") (class "Default")
      (node (ref "C5") (pin "4") (pinfunction "4_4") (pintype "passive"))
      (node (ref "R9") (pin "1") (pinfunction "1_1") (pintype "passive"))
      (node (ref "U3") (pin "5") (pinfunction "LIN1_N_5") (pintype "input"))
      (node (ref "U4") (pin "4") (pinfunction "ANODE2_4") (pintype "passive"))
      (node (ref "U4") (pin "6") (pinfunction "VO2_6") (pintype "output"))
    )
    (net (code "26") (name "/LIN2") (class "Default")
      (node (ref "C5") (pin "5") (pinfunction "5_5") (pintype "passive"))
      (node (ref "R12") (pin "1") (pinfunction "1_1") (pintype "passive"))
      (node (ref "U3") (pin "6") (pinfunction "LIN2_N_6") (pintype "input"))
      (node (ref "U5") (pin "1") (pinfunction "ANODE1_1") (pintype "passive"))
      (node (ref "U5") (pin "7") (pinfunction "VO1_7") (pintype "output"))
    )
    (net (code "27") (name "/LIN3") (class "Default")
      (node (ref "C5") (pin "6") (pinfunction "6_6") (pintype "passive"))
      (node (ref "R13") (pin "1") (pinfunction "1_1") (pintype "passive"))
      (node (ref "U3") (pin "7") (pinfunction "LIN3_N_7") (pintype "input"))
      (node (ref "U5") (pin "4") (pinfunction "ANODE2_4") (pintype "passive"))
      (node (ref "U5") (pin "6") (pinfunction "VO2_6") (pintype "output"))
    )
    (net (code "28") (name "/LO1") (class "Default")
      (node (ref "D7") (pin "1") (pinfunction "A_1") (pintype "passive"))
      (node (ref "R14") (pin "1") (pinfunction "1_1") (pintype "passive"))
      (node (ref "SA2") (pin "1") (pinfunction "G_1") (pintype "passive"))
    )
    (net (code "29") (name "/LO2") (class "Default")
      (node (ref "D8") (pin "1") (pinfunction "A_1") (pintype "passive"))
      (node (ref "R15") (pin "1") (pinfunction "1_1") (pintype "passive"))
      (node (ref "SB2") (pin "1") (pinfunction "G_1") (pintype "passive"))
    )
    (net (code "30") (name "/LO3") (class "Default")
      (node (ref "D9") (pin "1") (pinfunction "A_1") (pintype "passive"))
      (node (ref "R16") (pin "1") (pinfunction "1_1") (pintype "passive"))
      (node (ref "SC2") (pin "1") (pinfunction "G_1") (pintype "passive"))
    )
    (net (code "31") (name "/RCIN") (class "Default")
      (node (ref "C16") (pin "1") (pinfunction "1_1") (pintype "passive"))
      (node (ref "R6") (pin "1") (pinfunction "1_1") (pintype "passive"))
      (node (ref "U3") (pin "11") (pinfunction "RCIN_11") (pintype "passive"))
    )
    (net (code "32") (name "/VB1") (class "Default")
      (node (ref "C17") (pin "1") (pinfunction "1_1") (pintype "passive"))
      (node (ref "C18") (pin "1") (pinfunction "1_1") (pintype "passive"))
      (node (ref "D3") (pin "C") (pinfunction "K_C") (pintype "passive"))
      (node (ref "U3") (pin "28") (pinfunction "VB1_28") (pintype "power_in"))
    )
    (net (code "33") (name "/VB2") (class "Default")
      (node (ref "C19") (pin "1") (pinfunction "1_1") (pintype "passive"))
      (node (ref "C21") (pin "1") (pinfunction "1_1") (pintype "passive"))
      (node (ref "D2") (pin "C") (pinfunction "K_C") (pintype "passive"))
      (node (ref "U3") (pin "24") (pinfunction "VB2_24") (pintype "power_in"))
    )
    (net (code "34") (name "/VB3") (class "Default")
      (node (ref "C20") (pin "1") (pinfunction "1_1") (pintype "passive"))
      (node (ref "C22") (pin "1") (pinfunction "1_1") (pintype "passive"))
      (node (ref "D1") (pin "C") (pinfunction "K_C") (pintype "passive"))
      (node (ref "U3") (pin "20") (pinfunction "VB3_20") (pintype "power_in"))
    )
    (net (code "35") (name "GND") (class "Default")
      (node (ref "C13") (pin "2") (pinfunction "2_2") (pintype "passive"))
      (node (ref "C14") (pin "2") (pinfunction "2_2") (pintype "passive"))
      (node (ref "C5") (pin "8") (pinfunction "8_8") (pintype "passive"))
      (node (ref "H1") (pin "1") (pinfunction "1_1") (pintype "passive"))
      (node (ref "J1") (pin "1") (pinfunction "1_1") (pintype "passive"))
      (node (ref "J2") (pin "1") (pinfunction "1_1") (pintype "passive"))
      (node (ref "LED1") (pin "2") (pinfunction "2_2") (pintype "passive"))
      (node (ref "U1") (pin "1") (pinfunction "GND_1") (pintype "passive"))
      (node (ref "U2") (pin "2") (pinfunction "CATHODE1_2") (pintype "passive"))
      (node (ref "U2") (pin "3") (pinfunction "CATHODE2_3") (pintype "passive"))
      (node (ref "U4") (pin "2") (pinfunction "CATHODE1_2") (pintype "passive"))
      (node (ref "U4") (pin "3") (pinfunction "CATHODE2_3") (pintype "passive"))
      (node (ref "U5") (pin "2") (pinfunction "CATHODE1_2") (pintype "passive"))
      (node (ref "U5") (pin "3") (pinfunction "CATHODE2_3") (pintype "passive"))
    )
    (net (code "36") (name "Net-(D4-K)") (class "Default")
      (node (ref "D4") (pin "2") (pinfunction "K_2") (pintype "passive"))
      (node (ref "R8") (pin "2") (pinfunction "2_2") (pintype "passive"))
      (node (ref "U3") (pin "27") (pinfunction "HO1_27") (pintype "output"))
    )
    (net (code "37") (name "Net-(D5-K)") (class "Default")
      (node (ref "D5") (pin "2") (pinfunction "K_2") (pintype "passive"))
      (node (ref "R10") (pin "2") (pinfunction "2_2") (pintype "passive"))
      (node (ref "U3") (pin "23") (pinfunction "HO2_23") (pintype "output"))
    )
    (net (code "38") (name "Net-(D6-K)") (class "Default")
      (node (ref "D6") (pin "2") (pinfunction "K_2") (pintype "passive"))
      (node (ref "R11") (pin "2") (pinfunction "2_2") (pintype "passive"))
      (node (ref "U3") (pin "19") (pinfunction "HO3_19") (pintype "output"))
    )
    (net (code "39") (name "Net-(D7-K)") (class "Default")
      (node (ref "D7") (pin "2") (pinfunction "K_2") (pintype "passive"))
      (node (ref "R14") (pin "2") (pinfunction "2_2") (pintype "passive"))
      (node (ref "U3") (pin "16") (pinfunction "LO1_16") (pintype "output"))
    )
    (net (code "40") (name "Net-(D8-K)") (class "Default")
      (node (ref "D8") (pin "2") (pinfunction "K_2") (pintype "passive"))
      (node (ref "R15") (pin "2") (pinfunction "2_2") (pintype "passive"))
      (node (ref "U3") (pin "15") (pinfunction "LO2_15") (pintype "output"))
    )
    (net (code "41") (name "Net-(D9-K)") (class "Default")
      (node (ref "D9") (pin "2") (pinfunction "K_2") (pintype "passive"))
      (node (ref "R16") (pin "2") (pinfunction "2_2") (pintype "passive"))
      (node (ref "U3") (pin "14") (pinfunction "LO3_14") (pintype "output"))
    )
    (net (code "42") (name "Net-(LED1-Pad1)") (class "Default")
      (node (ref "LED1") (pin "1") (pinfunction "1_1") (pintype "passive"))
      (node (ref "R1") (pin "1") (pinfunction "1_1") (pintype "passive"))
    )
    (net (code "43") (name "Net-(LED2-Pad1)") (class "Default")
      (node (ref "LED2") (pin "1") (pinfunction "1_1") (pintype "passive"))
      (node (ref "R2") (pin "1") (pinfunction "1_1") (pintype "passive"))
    )
    (net (code "44") (name "Net-(LED3-Pad2)") (class "Default")
      (node (ref "LED3") (pin "2") (pinfunction "2_2") (pintype "passive"))
      (node (ref "R4") (pin "1") (pinfunction "1_1") (pintype "passive"))
    )
    (net (code "45") (name "Net-(SB1-E)") (class "Default")
      (node (ref "SB1") (pin "3") (pinfunction "E_3") (pintype "passive"))
      (node (ref "SB2") (pin "2") (pinfunction "C_2") (pintype "passive"))
    )
    (net (code "46") (name "Net-(SC1-E)") (class "Default")
      (node (ref "SC1") (pin "3") (pinfunction "E_3") (pintype "passive"))
      (node (ref "SC2") (pin "2") (pinfunction "C_2") (pintype "passive"))
    )
    (net (code "47") (name "Net-(U3-COM)") (class "Default")
      (node (ref "C30") (pin "2") (pinfunction "2_2") (pintype "passive"))
      (node (ref "C31") (pin "2") (pinfunction "2_2") (pintype "passive"))
      (node (ref "R18") (pin "2") (pinfunction "2_2") (pintype "passive"))
      (node (ref "U3") (pin "13") (pinfunction "COM_13") (pintype "power_in"))
    )
    (net (code "48") (name "unconnected-(R19-Pad1)") (class "Default")
      (node (ref "R19") (pin "1") (pinfunction "1_1") (pintype "passive+no_connect"))
    )
  )
)
